# Photo-Diode_Board.net
KiCad netlist of a schematic drawn in Altium Designer
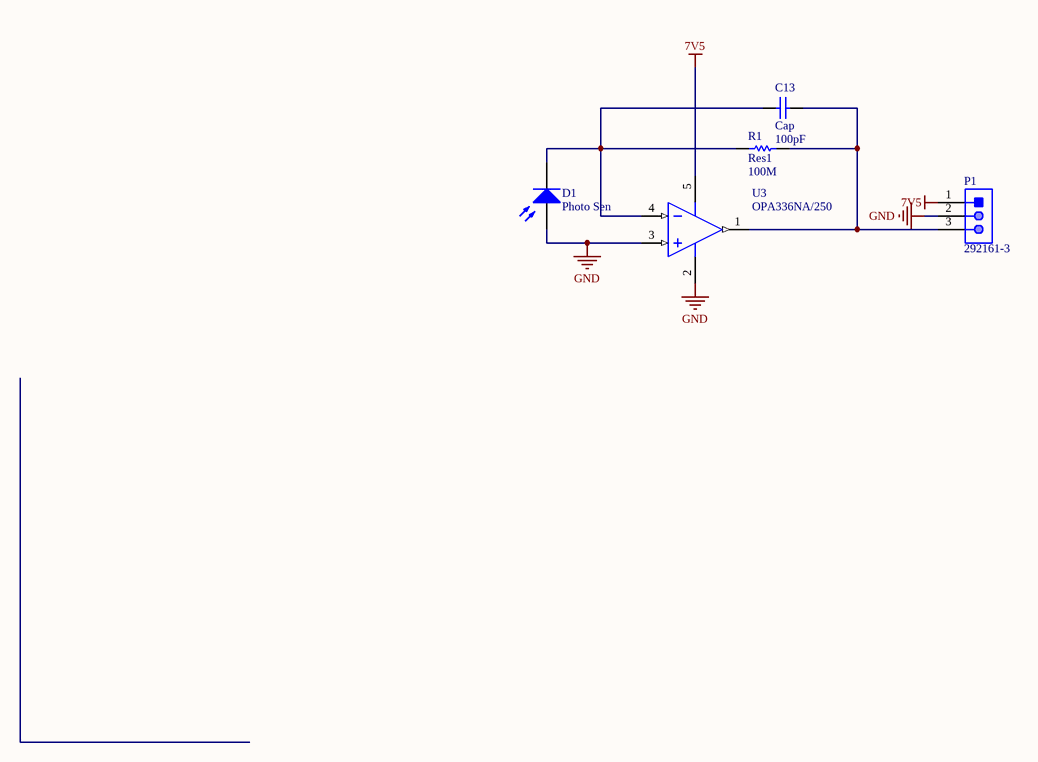
[diagram p0: Photo-Diode Board.SchDoc]

(export (version "E")
  (design (tool "Eeschema 10.0.6"))
  (components
    (comp (ref "C13")
      (value "Cap")
      (footprint "0402-A")
      (description "Capacitor")
      (fields (field (name "ALTIUM_VALUE") "100pF") (field (name "PUBLISHER") "Altium Limited"))
      (libsource (lib "Miscellaneous Devices") (part "Cap"))
    )
    (comp (ref "D1")
      (value "Photo Sen")
      (footprint "TO-18")
      (description "Photosensitive Diode")
      (fields (field (name "PUBLISHER") "Altium Limited"))
      (libsource (lib "Miscellaneous Devices") (part "Photo Sen"))
    )
    (comp (ref "P1")
      (value "292161-3")
      (footprint "TECO-292161-3_V")
      (fields (field (name "MANUFACTURER") "TE Connectivity"))
      (libsource (lib "Altium Content Vault") (part "CN-1P-M-R3"))
    )
    (comp (ref "R1")
      (value "Res1")
      (footprint "1608[0603]")
      (description "Resistor")
      (fields (field (name "ALTIUM_VALUE") "100M") (field (name "PUBLISHER") "Altium Limited"))
      (libsource (lib "Miscellaneous Devices") (part "Res1"))
    )
    (comp (ref "U3")
      (value "OPA336NA/250")
      (footprint "DBV0005A_M")
      (fields (field (name "MANUFACTURER") "Texas Instruments"))
      (libsource (lib "Altium Content Vault") (part "TI-OPA_SM7XXXX-DBV5"))
    )
  )
  (nets
    (net (code "1") (name "7V5") (class "Default")
      (node (ref "P1") (pin "1") (pinfunction "1_1") (pintype "passive"))
      (node (ref "U3") (pin "5") (pinfunction "V+_5") (pintype "power_in"))
    )
    (net (code "2") (name "GND") (class "Default")
      (node (ref "D1") (pin "1") (pinfunction "A_1") (pintype "passive"))
      (node (ref "P1") (pin "2") (pinfunction "2_2") (pintype "passive"))
      (node (ref "U3") (pin "2") (pinfunction "V-_2") (pintype "power_in"))
      (node (ref "U3") (pin "3") (pinfunction "IN+_3") (pintype "input"))
    )
    (net (code "3") (name "Net-(D1-K)") (class "Default")
      (node (ref "C13") (pin "1") (pinfunction "1_1") (pintype "passive"))
      (node (ref "D1") (pin "2") (pinfunction "K_2") (pintype "passive"))
      (node (ref "R1") (pin "1") (pinfunction "1_1") (pintype "passive"))
      (node (ref "U3") (pin "4") (pinfunction "IN-_4") (pintype "input"))
    )
    (net (code "4") (name "Net-(U3-OUT)") (class "Default")
      (node (ref "C13") (pin "2") (pinfunction "2_2") (pintype "passive"))
      (node (ref "P1") (pin "3") (pinfunction "3_3") (pintype "passive"))
      (node (ref "R1") (pin "2") (pinfunction "2_2") (pintype "passive"))
      (node (ref "U3") (pin "1") (pinfunction "OUT_1") (pintype "output"))
    )
  )
)
